# PAGE19.net
KiCad netlist of a schematic drawn in Altium Designer
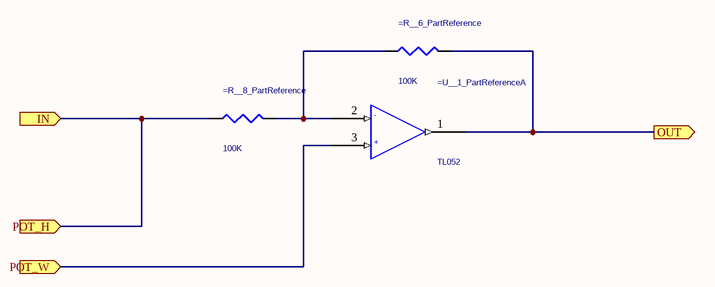
[diagram p0: PAGE19.SchDoc]

(export (version "E")
  (design (tool "Eeschema 10.0.6"))
  (components
    (comp (ref "=R__6_PartReference") (value "100K") (libsource (lib "*") (part "R_Dup1")))
    (comp (ref "=R__8_PartReference") (value "100K") (libsource (lib "*") (part "R_Dup1")))
    (comp (ref "=U__1_PartReference")
      (value "TL052")
      (footprint "DIP8")
      (libsource (lib "*") (part "GEN DUAL OPAMP-H"))
    )
  )
  (nets
    (net (code "1") (name "/IN") (class "Default")
      (node (ref "=R__8_PartReference") (pin "1") (pinfunction "1_1") (pintype "passive"))
    )
    (net (code "2") (name "/OUT") (class "Default")
      (node (ref "=R__6_PartReference") (pin "2") (pinfunction "2_2") (pintype "passive"))
      (node (ref "=U__1_PartReference") (pin "1") (pinfunction "OUT_1") (pintype "output"))
    )
    (net (code "3") (name "/POT_W") (class "Default")
      (node (ref "=U__1_PartReference") (pin "3") (pinfunction "+_3") (pintype "input"))
    )
    (net (code "4") (name "Net-(=U__1_PartReferenceA--)") (class "Default")
      (node (ref "=R__6_PartReference") (pin "1") (pinfunction "1_1") (pintype "passive"))
      (node (ref "=R__8_PartReference") (pin "2") (pinfunction "2_2") (pintype "passive"))
      (node (ref "=U__1_PartReference") (pin "2") (pinfunction "-_2") (pintype "input"))
    )
  )
)
